# PhatStats_Slim_Enclosure_QTPY_PCB_v1_00_.net
KiCad netlist of a schematic drawn in EAGLE
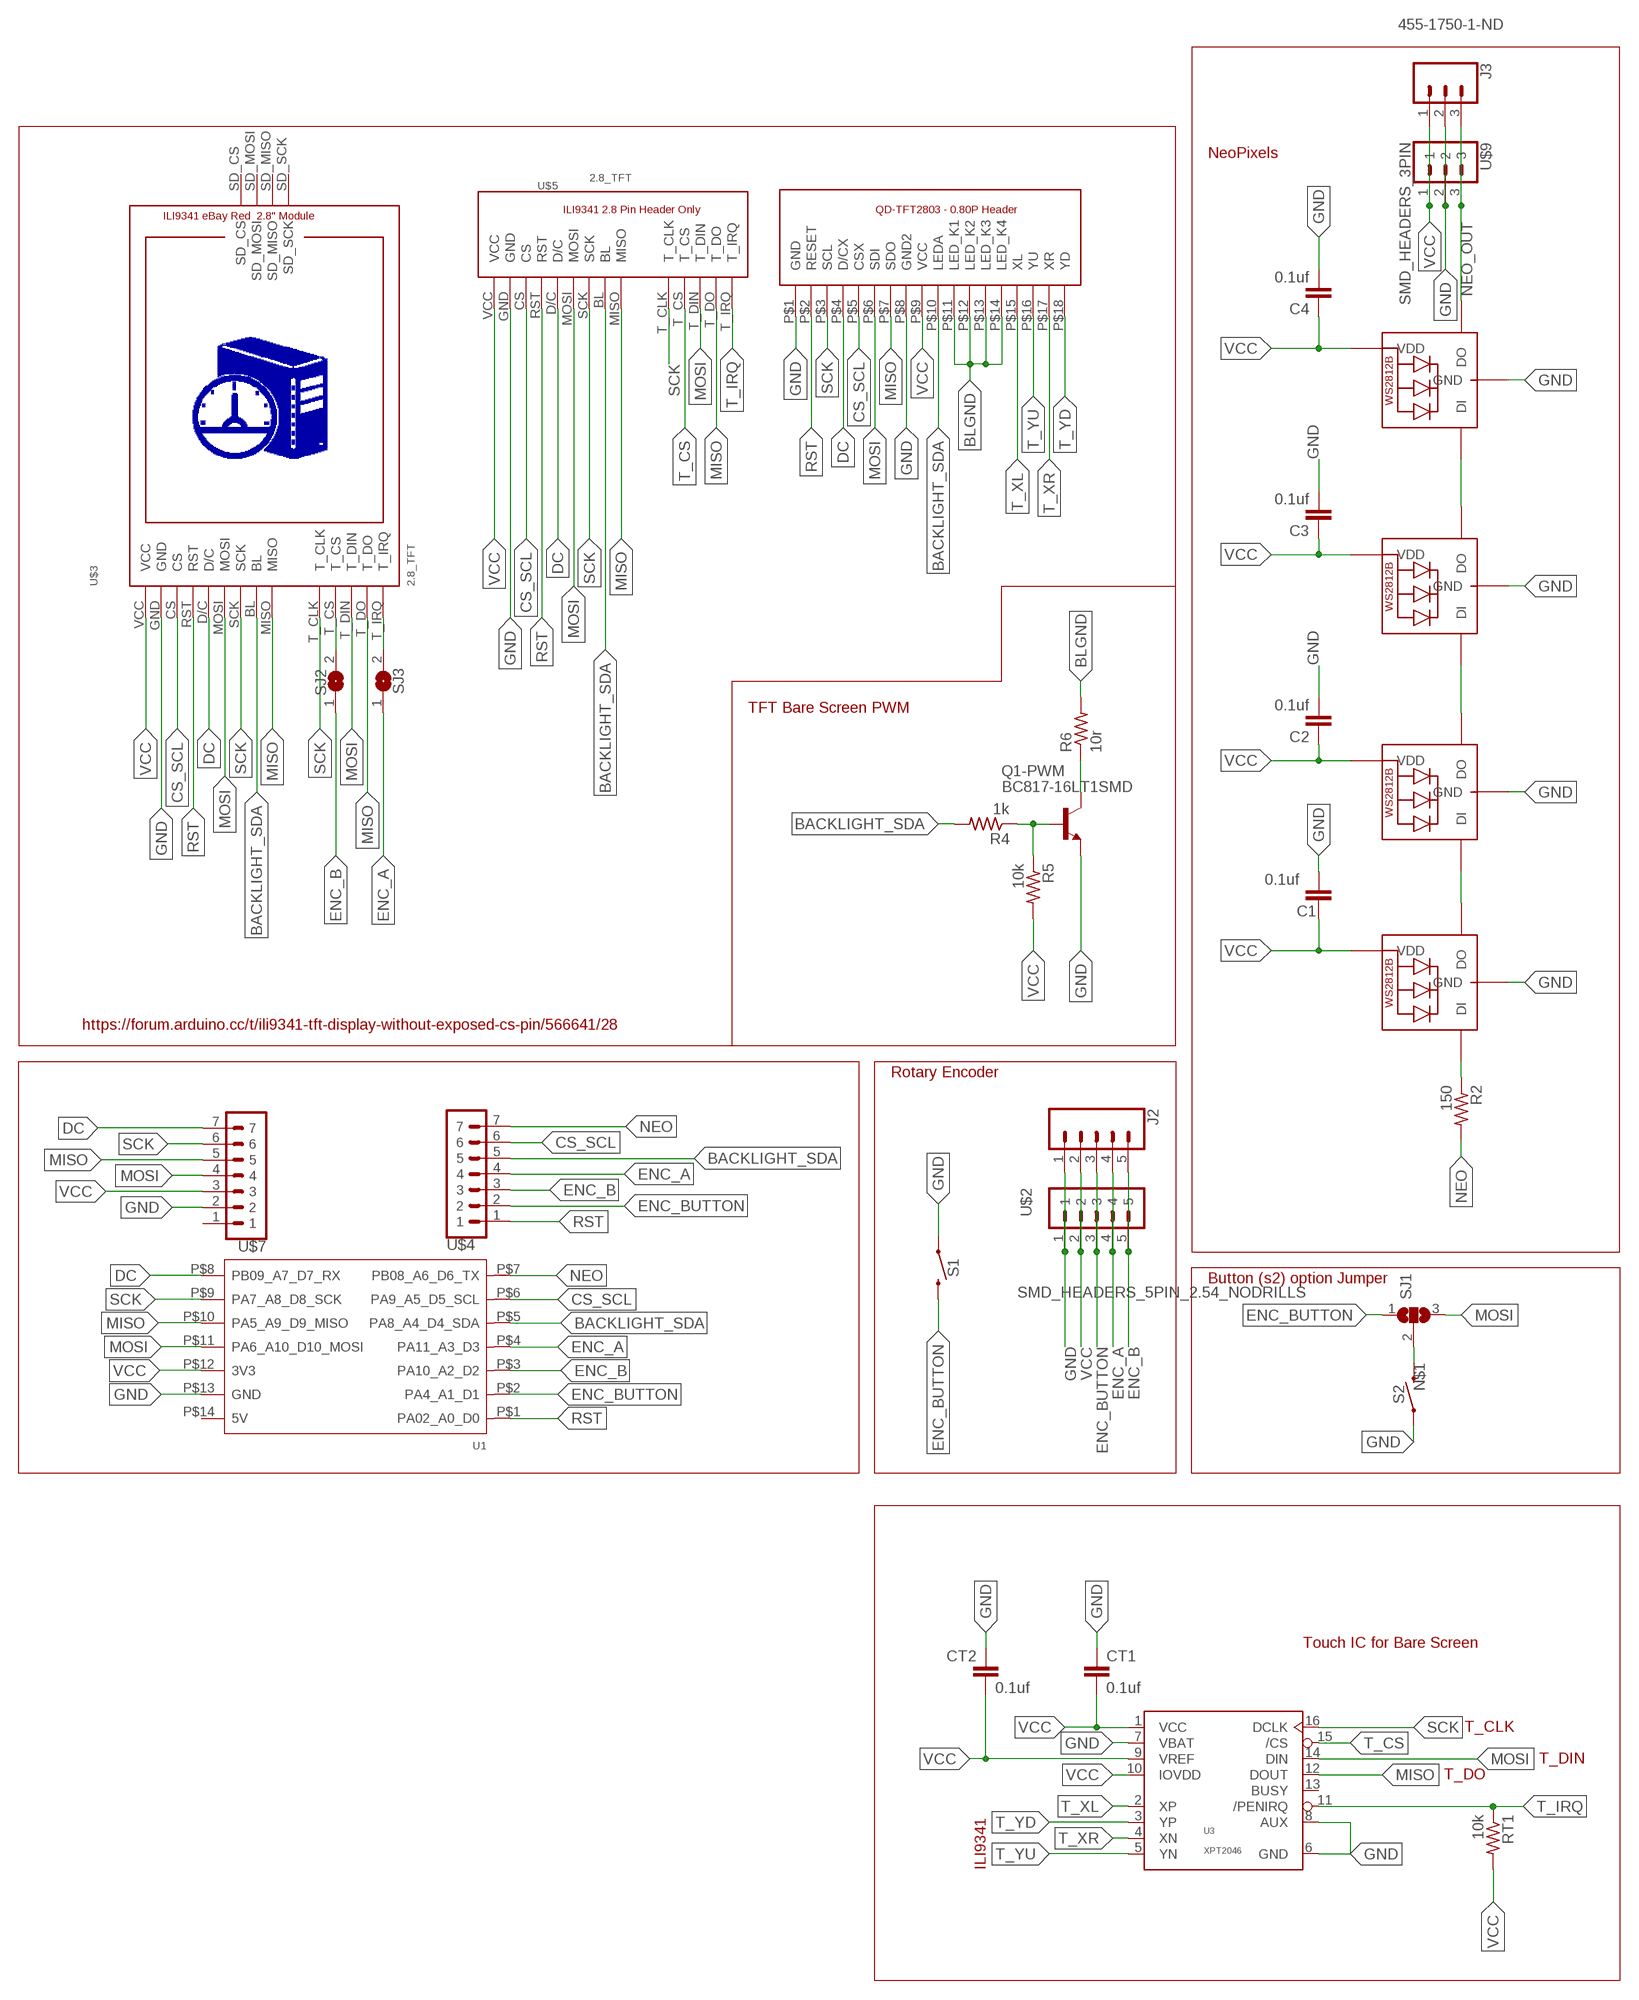
[diagram p0: schematic, sheet 1]

(export (version "E")
  (design (tool "Eeschema 10.0.6"))
  (components
    (comp (ref "0")
      (value "ILI9341-2.8")
      (footprint "eagle-import:ILI9341-2.8")
      (libsource (lib "eagle-import") (part "ILI9341-2.8"))
    )
    (comp (ref "C1")
      (value "0.1uf")
      (footprint "eagle-import:C1206")
      (libsource (lib "eagle-import") (part "C-EUC1206"))
    )
    (comp (ref "C2")
      (value "0.1uf")
      (footprint "eagle-import:C1206")
      (libsource (lib "eagle-import") (part "C-EUC1206"))
    )
    (comp (ref "C3")
      (value "0.1uf")
      (footprint "eagle-import:C1206")
      (libsource (lib "eagle-import") (part "C-EUC1206"))
    )
    (comp (ref "C4")
      (value "0.1uf")
      (footprint "eagle-import:C1206")
      (libsource (lib "eagle-import") (part "C-EUC1206"))
    )
    (comp (ref "CT1")
      (value "0.1uf")
      (footprint "eagle-import:C1206")
      (libsource (lib "eagle-import") (part "C-EUC1206"))
    )
    (comp (ref "CT2")
      (value "0.1uf")
      (footprint "eagle-import:C1206")
      (libsource (lib "eagle-import") (part "C-EUC1206"))
    )
    (comp (ref "J2")
      (value "CONN_05")
      (footprint "eagle-import:1X05")
      (libsource (lib "eagle-import") (part "CONN_05"))
    )
    (comp (ref "J3")
      (value "455-1750-1-ND")
      (footprint "eagle-import:1X03")
      (libsource (lib "eagle-import") (part "CONN_03"))
    )
    (comp (ref "NEO1")
      (value "WS2812B5050")
      (footprint "eagle-import:WS2812B")
      (libsource (lib "eagle-import") (part "WS2812B5050"))
    )
    (comp (ref "NEO2")
      (value "WS2812B5050")
      (footprint "eagle-import:WS2812B")
      (libsource (lib "eagle-import") (part "WS2812B5050"))
    )
    (comp (ref "NEO3")
      (value "WS2812B5050")
      (footprint "eagle-import:WS2812B")
      (libsource (lib "eagle-import") (part "WS2812B5050"))
    )
    (comp (ref "NEO4")
      (value "WS2812B5050")
      (footprint "eagle-import:WS2812B")
      (libsource (lib "eagle-import") (part "WS2812B5050"))
    )
    (comp (ref "Q1-PWM")
      (value "BC817-16LT1SMD")
      (footprint "eagle-import:SOT23-BEC")
      (libsource (lib "eagle-import") (part "BC817SMD-16LT1"))
    )
    (comp (ref "R2")
      (value "150")
      (footprint "eagle-import:M1206")
      (libsource (lib "eagle-import") (part "R-US_M1206"))
    )
    (comp (ref "R4")
      (value "1k")
      (footprint "eagle-import:M1206")
      (libsource (lib "eagle-import") (part "R-US_M1206"))
    )
    (comp (ref "R5")
      (value "10k")
      (footprint "eagle-import:M1206")
      (libsource (lib "eagle-import") (part "R-US_M1206"))
    )
    (comp (ref "R6")
      (value "10r")
      (footprint "eagle-import:M1206")
      (libsource (lib "eagle-import") (part "R-US_M1206"))
    )
    (comp (ref "RT1")
      (value "10k")
      (footprint "eagle-import:M1206")
      (libsource (lib "eagle-import") (part "R-US_M1206"))
    )
    (comp (ref "S1")
      (value "MOMENTARY-SWITCH-SPST-SMD-6.2MM-TALL")
      (footprint "eagle-import:TACTILE_SWITCH_SMD_6.2MM_TALL")
      (libsource (lib "eagle-import") (part "MOMENTARY-SWITCH-SPST-SMD-6.2MM-TALL"))
    )
    (comp (ref "S2")
      (value "MOMENTARY-SWITCH-SPST-SMD-6.2MM-TALL")
      (footprint "eagle-import:TACTILE_SWITCH_SMD_6.2MM_TALL")
      (libsource (lib "eagle-import") (part "MOMENTARY-SWITCH-SPST-SMD-6.2MM-TALL"))
    )
    (comp (ref "SJ1")
      (value "SJ2W")
      (footprint "eagle-import:SJ_2")
      (libsource (lib "eagle-import") (part "SJ2W"))
    )
    (comp (ref "SJ2") (value "SJ") (footprint "eagle-import:SJ") (libsource (lib "eagle-import") (part "SJ")))
    (comp (ref "SJ3") (value "SJ") (footprint "eagle-import:SJ") (libsource (lib "eagle-import") (part "SJ")))
    (comp (ref "U$2")
      (value "SMD_HEADERS_5PIN_2.54_NODRILLS")
      (footprint "eagle-import:SMD_HEADERS_5PIN")
      (libsource (lib "eagle-import") (part "SMD_HEADERS_5PIN_2.54_NODRILLS"))
    )
    (comp (ref "U$3")
      (value "2.8_TFT")
      (footprint "eagle-import:2.8_TFT")
      (libsource (lib "eagle-import") (part "2.8_TFT"))
    )
    (comp (ref "U$4")
      (value "SMD_HEADERS_7PIN_2.54_NODRILLS")
      (footprint "eagle-import:SMD_HEADERS_7PIN")
      (libsource (lib "eagle-import") (part "SMD_HEADERS_7PIN_2.54_NODRILLS"))
    )
    (comp (ref "U$5")
      (value "2.8_TFT")
      (footprint "eagle-import:2.8_TFT")
      (libsource (lib "eagle-import") (part "TML_ili9341-2.8_tft-display_PinHeader only_2.8_TFT"))
    )
    (comp (ref "U$7")
      (value "SMD_HEADERS_7PIN_2.54_NODRILLS")
      (footprint "eagle-import:SMD_HEADERS_7PIN")
      (libsource (lib "eagle-import") (part "SMD_HEADERS_7PIN_2.54_NODRILLS"))
    )
    (comp (ref "U$9")
      (value "SMD_HEADERS_3PIN")
      (footprint "eagle-import:SMD_HEADERS_3PIN")
      (libsource (lib "eagle-import") (part "SMD_HEADERS_3PIN"))
    )
    (comp (ref "U1")
      (value "MOUDLE-SEEEDUINO-XIAO")
      (footprint "eagle-import:MOUDLE14P-2.54-21X17.8MM")
      (libsource (lib "eagle-import") (part "MOUDLE-SEEEDUINO-XIAO"))
    )
    (comp (ref "U3")
      (value "XPT2046")
      (footprint "eagle-import:TSSOP-16")
      (fields (field (name "MF") "Xptek"))
      (libsource (lib "eagle-import") (part "XPT2046"))
    )
  )
  (nets
    (net (code "1") (name "/N$1") (class "Default")
      (node (ref "S2") (pin "B2") (pinfunction "2_B2") (pintype "passive"))
      (node (ref "SJ1") (pin "2") (pinfunction "2_2") (pintype "passive"))
    )
    (net (code "2") (name "/NEO_OUT") (class "Default")
      (node (ref "J3") (pin "3") (pinfunction "3_3") (pintype "passive"))
      (node (ref "NEO4") (pin "2-DOUT") (pinfunction "DO_2-DOUT") (pintype "output"))
      (node (ref "U$9") (pin "3") (pinfunction "3_3") (pintype "passive"))
    )
    (net (code "3") (name "BACKLIGHT_SDA") (class "Default")
      (node (ref "0") (pin "P$10") (pinfunction "LEDA_P$10") (pintype "bidirectional"))
      (node (ref "R4") (pin "2") (pinfunction "2_2") (pintype "passive"))
      (node (ref "U$3") (pin "BL") (pinfunction "BL_BL") (pintype "bidirectional"))
      (node (ref "U$4") (pin "5") (pinfunction "5_5") (pintype "passive"))
      (node (ref "U$5") (pin "BL") (pinfunction "BL_BL") (pintype "bidirectional"))
      (node (ref "U1") (pin "P$5") (pinfunction "PA8_A4_D4_SDA_P$5") (pintype "bidirectional"))
    )
    (net (code "4") (name "BLGND") (class "Default")
      (node (ref "0") (pin "P$11") (pinfunction "LED_K1_P$11") (pintype "bidirectional"))
      (node (ref "0") (pin "P$12") (pinfunction "LED_K2_P$12") (pintype "bidirectional"))
      (node (ref "0") (pin "P$13") (pinfunction "LED_K3_P$13") (pintype "bidirectional"))
      (node (ref "0") (pin "P$14") (pinfunction "LED_K4_P$14") (pintype "bidirectional"))
      (node (ref "R6") (pin "2") (pinfunction "2_2") (pintype "passive"))
    )
    (net (code "5") (name "CS_SCL") (class "Default")
      (node (ref "0") (pin "P$5") (pinfunction "CSX_P$5") (pintype "bidirectional"))
      (node (ref "U$3") (pin "CS") (pinfunction "CS_CS") (pintype "bidirectional"))
      (node (ref "U$4") (pin "6") (pinfunction "6_6") (pintype "passive"))
      (node (ref "U$5") (pin "CS") (pinfunction "CS_CS") (pintype "bidirectional"))
      (node (ref "U1") (pin "P$6") (pinfunction "PA9_A5_D5_SCL_P$6") (pintype "bidirectional"))
    )
    (net (code "6") (name "DC") (class "Default")
      (node (ref "0") (pin "P$4") (pinfunction "D/CX_P$4") (pintype "bidirectional"))
      (node (ref "U$3") (pin "D/C") (pinfunction "D/C_D/C") (pintype "bidirectional"))
      (node (ref "U$5") (pin "D/C") (pinfunction "D/C_D/C") (pintype "bidirectional"))
      (node (ref "U$7") (pin "7") (pinfunction "7_7") (pintype "passive"))
      (node (ref "U1") (pin "P$8") (pinfunction "PB09_A7_D7_RX_P$8") (pintype "bidirectional"))
    )
    (net (code "7") (name "ENC_A") (class "Default")
      (node (ref "J2") (pin "4") (pinfunction "4_4") (pintype "passive"))
      (node (ref "SJ3") (pin "1") (pinfunction "1_1") (pintype "passive"))
      (node (ref "U$2") (pin "4") (pinfunction "4_4") (pintype "passive"))
      (node (ref "U$4") (pin "4") (pinfunction "4_4") (pintype "passive"))
      (node (ref "U1") (pin "P$4") (pinfunction "PA11_A3_D3_P$4") (pintype "bidirectional"))
    )
    (net (code "8") (name "ENC_B") (class "Default")
      (node (ref "J2") (pin "5") (pinfunction "5_5") (pintype "passive"))
      (node (ref "SJ2") (pin "1") (pinfunction "1_1") (pintype "passive"))
      (node (ref "U$2") (pin "5") (pinfunction "5_5") (pintype "passive"))
      (node (ref "U$4") (pin "3") (pinfunction "3_3") (pintype "passive"))
      (node (ref "U1") (pin "P$3") (pinfunction "PA10_A2_D2_P$3") (pintype "bidirectional"))
    )
    (net (code "9") (name "ENC_BUTTON") (class "Default")
      (node (ref "J2") (pin "3") (pinfunction "3_3") (pintype "passive"))
      (node (ref "S1") (pin "B2") (pinfunction "2_B2") (pintype "passive"))
      (node (ref "SJ1") (pin "1") (pinfunction "1_1") (pintype "passive"))
      (node (ref "U$2") (pin "3") (pinfunction "3_3") (pintype "passive"))
      (node (ref "U$4") (pin "2") (pinfunction "2_2") (pintype "passive"))
      (node (ref "U1") (pin "P$2") (pinfunction "PA4_A1_D1_P$2") (pintype "bidirectional"))
    )
    (net (code "10") (name "GND") (class "Default")
      (node (ref "0") (pin "P$1") (pinfunction "GND_P$1") (pintype "bidirectional"))
      (node (ref "0") (pin "P$8") (pinfunction "GND2_P$8") (pintype "bidirectional"))
      (node (ref "C1") (pin "1") (pinfunction "1_1") (pintype "passive"))
      (node (ref "C2") (pin "2") (pinfunction "2_2") (pintype "passive"))
      (node (ref "C3") (pin "2") (pinfunction "2_2") (pintype "passive"))
      (node (ref "C4") (pin "2") (pinfunction "2_2") (pintype "passive"))
      (node (ref "CT1") (pin "1") (pinfunction "1_1") (pintype "passive"))
      (node (ref "CT2") (pin "1") (pinfunction "1_1") (pintype "passive"))
      (node (ref "J2") (pin "1") (pinfunction "1_1") (pintype "passive"))
      (node (ref "J3") (pin "2") (pinfunction "2_2") (pintype "passive"))
      (node (ref "NEO1") (pin "3-GND") (pinfunction "GND_3-GND") (pintype "power_in"))
      (node (ref "NEO2") (pin "3-GND") (pinfunction "GND_3-GND") (pintype "power_in"))
      (node (ref "NEO3") (pin "3-GND") (pinfunction "GND_3-GND") (pintype "power_in"))
      (node (ref "NEO4") (pin "3-GND") (pinfunction "GND_3-GND") (pintype "power_in"))
      (node (ref "Q1-PWM") (pin "E") (pinfunction "E_E") (pintype "passive"))
      (node (ref "S1") (pin "A2") (pinfunction "1_A2") (pintype "passive"))
      (node (ref "S2") (pin "A2") (pinfunction "1_A2") (pintype "passive"))
      (node (ref "U$2") (pin "1") (pinfunction "1_1") (pintype "passive"))
      (node (ref "U$3") (pin "GND") (pinfunction "GND_GND") (pintype "bidirectional"))
      (node (ref "U$5") (pin "GND") (pinfunction "GND_GND") (pintype "bidirectional"))
      (node (ref "U$7") (pin "2") (pinfunction "2_2") (pintype "passive"))
      (node (ref "U$9") (pin "2") (pinfunction "2_2") (pintype "passive"))
      (node (ref "U1") (pin "P$13") (pinfunction "GND_P$13") (pintype "bidirectional"))
      (node (ref "U3") (pin "6") (pinfunction "GND_6") (pintype "power_in"))
      (node (ref "U3") (pin "7") (pinfunction "VBAT_7") (pintype "input"))
      (node (ref "U3") (pin "8") (pinfunction "AUX_8") (pintype "input"))
    )
    (net (code "11") (name "MISO") (class "Default")
      (node (ref "0") (pin "P$7") (pinfunction "SDO_P$7") (pintype "bidirectional"))
      (node (ref "U$3") (pin "MISO") (pinfunction "MISO_MISO") (pintype "bidirectional"))
      (node (ref "U$3") (pin "T_DO") (pinfunction "T_DO_T_DO") (pintype "bidirectional"))
      (node (ref "U$5") (pin "MISO") (pinfunction "MISO_MISO") (pintype "bidirectional"))
      (node (ref "U$5") (pin "T_DO") (pinfunction "T_DO_T_DO") (pintype "bidirectional"))
      (node (ref "U$7") (pin "5") (pinfunction "5_5") (pintype "passive"))
      (node (ref "U1") (pin "P$10") (pinfunction "PA5_A9_D9_MISO_P$10") (pintype "bidirectional"))
      (node (ref "U3") (pin "12") (pinfunction "DOUT_12") (pintype "output"))
    )
    (net (code "12") (name "MOSI") (class "Default")
      (node (ref "0") (pin "P$6") (pinfunction "SDI_P$6") (pintype "bidirectional"))
      (node (ref "SJ1") (pin "3") (pinfunction "3_3") (pintype "passive"))
      (node (ref "U$3") (pin "MOSI") (pinfunction "MOSI_MOSI") (pintype "bidirectional"))
      (node (ref "U$3") (pin "T_DIN") (pinfunction "T_DIN_T_DIN") (pintype "bidirectional"))
      (node (ref "U$5") (pin "MOSI") (pinfunction "MOSI_MOSI") (pintype "bidirectional"))
      (node (ref "U$5") (pin "T_DIN") (pinfunction "T_DIN_T_DIN") (pintype "bidirectional"))
      (node (ref "U$7") (pin "4") (pinfunction "4_4") (pintype "passive"))
      (node (ref "U1") (pin "P$11") (pinfunction "PA6_A10_D10_MOSI_P$11") (pintype "bidirectional"))
      (node (ref "U3") (pin "14") (pinfunction "DIN_14") (pintype "input"))
    )
    (net (code "13") (name "NEO") (class "Default")
      (node (ref "R2") (pin "2") (pinfunction "2_2") (pintype "passive"))
      (node (ref "U$4") (pin "7") (pinfunction "7_7") (pintype "passive"))
      (node (ref "U1") (pin "P$7") (pinfunction "PB08_A6_D6_TX_P$7") (pintype "bidirectional"))
    )
    (net (code "14") (name "Net-(NEO1-DI)") (class "Default")
      (node (ref "NEO1") (pin "4-DIN") (pinfunction "DI_4-DIN") (pintype "input"))
      (node (ref "R2") (pin "1") (pinfunction "1_1") (pintype "passive"))
    )
    (net (code "15") (name "Net-(NEO1-DO)") (class "Default")
      (node (ref "NEO1") (pin "2-DOUT") (pinfunction "DO_2-DOUT") (pintype "output"))
      (node (ref "NEO2") (pin "4-DIN") (pinfunction "DI_4-DIN") (pintype "input"))
    )
    (net (code "16") (name "Net-(NEO2-DO)") (class "Default")
      (node (ref "NEO2") (pin "2-DOUT") (pinfunction "DO_2-DOUT") (pintype "output"))
      (node (ref "NEO3") (pin "4-DIN") (pinfunction "DI_4-DIN") (pintype "input"))
    )
    (net (code "17") (name "Net-(NEO3-DO)") (class "Default")
      (node (ref "NEO3") (pin "2-DOUT") (pinfunction "DO_2-DOUT") (pintype "output"))
      (node (ref "NEO4") (pin "4-DIN") (pinfunction "DI_4-DIN") (pintype "input"))
    )
    (net (code "18") (name "Net-(Q1-PWM-PadB)") (class "Default")
      (node (ref "Q1-PWM") (pin "B") (pinfunction "B_B") (pintype "passive"))
      (node (ref "R4") (pin "1") (pinfunction "1_1") (pintype "passive"))
      (node (ref "R5") (pin "1") (pinfunction "1_1") (pintype "passive"))
    )
    (net (code "19") (name "Net-(Q1-PWM-PadC)") (class "Default")
      (node (ref "Q1-PWM") (pin "C") (pinfunction "C_C") (pintype "passive"))
      (node (ref "R6") (pin "1") (pinfunction "1_1") (pintype "passive"))
    )
    (net (code "20") (name "RST") (class "Default")
      (node (ref "0") (pin "P$2") (pinfunction "RESET_P$2") (pintype "bidirectional"))
      (node (ref "U$3") (pin "RST") (pinfunction "RST_RST") (pintype "bidirectional"))
      (node (ref "U$4") (pin "1") (pinfunction "1_1") (pintype "passive"))
      (node (ref "U$5") (pin "RST") (pinfunction "RST_RST") (pintype "bidirectional"))
      (node (ref "U1") (pin "P$1") (pinfunction "PA02_A0_D0_P$1") (pintype "bidirectional"))
    )
    (net (code "21") (name "SCK") (class "Default")
      (node (ref "0") (pin "P$3") (pinfunction "SCL_P$3") (pintype "bidirectional"))
      (node (ref "U$3") (pin "SCK") (pinfunction "SCK_SCK") (pintype "bidirectional"))
      (node (ref "U$3") (pin "T_CLK") (pinfunction "T_CLK_T_CLK") (pintype "bidirectional"))
      (node (ref "U$5") (pin "SCK") (pinfunction "SCK_SCK") (pintype "bidirectional"))
      (node (ref "U$5") (pin "T_CLK") (pinfunction "T_CLK_T_CLK") (pintype "bidirectional"))
      (node (ref "U$7") (pin "6") (pinfunction "6_6") (pintype "passive"))
      (node (ref "U1") (pin "P$9") (pinfunction "PA7_A8_D8_SCK_P$9") (pintype "bidirectional"))
      (node (ref "U3") (pin "16") (pinfunction "DCLK_16") (pintype "input"))
    )
    (net (code "22") (name "T_CS") (class "Default")
      (node (ref "SJ2") (pin "2") (pinfunction "2_2") (pintype "passive"))
      (node (ref "U$3") (pin "T_CS") (pinfunction "T_CS_T_CS") (pintype "bidirectional"))
      (node (ref "U$5") (pin "T_CS") (pinfunction "T_CS_T_CS") (pintype "bidirectional"))
      (node (ref "U3") (pin "15") (pinfunction "/CS_15") (pintype "input"))
    )
    (net (code "23") (name "T_IRQ") (class "Default")
      (node (ref "RT1") (pin "1") (pinfunction "1_1") (pintype "passive"))
      (node (ref "SJ3") (pin "2") (pinfunction "2_2") (pintype "passive"))
      (node (ref "U$3") (pin "T_IRQ") (pinfunction "T_IRQ_T_IRQ") (pintype "bidirectional"))
      (node (ref "U$5") (pin "T_IRQ") (pinfunction "T_IRQ_T_IRQ") (pintype "bidirectional"))
      (node (ref "U3") (pin "11") (pinfunction "/PENIRQ_11") (pintype "output"))
    )
    (net (code "24") (name "T_XL") (class "Default")
      (node (ref "0") (pin "P$15") (pinfunction "XL_P$15") (pintype "bidirectional"))
      (node (ref "U3") (pin "2") (pinfunction "XP_2") (pintype "input"))
    )
    (net (code "25") (name "T_XR") (class "Default")
      (node (ref "0") (pin "P$17") (pinfunction "XR_P$17") (pintype "bidirectional"))
      (node (ref "U3") (pin "4") (pinfunction "XN_4") (pintype "input"))
    )
    (net (code "26") (name "T_YD") (class "Default")
      (node (ref "0") (pin "P$18") (pinfunction "YD_P$18") (pintype "bidirectional"))
      (node (ref "U3") (pin "3") (pinfunction "YP_3") (pintype "input"))
    )
    (net (code "27") (name "T_YU") (class "Default")
      (node (ref "0") (pin "P$16") (pinfunction "YU_P$16") (pintype "bidirectional"))
      (node (ref "U3") (pin "5") (pinfunction "YN_5") (pintype "input"))
    )
    (net (code "28") (name "VCC") (class "Default")
      (node (ref "0") (pin "P$9") (pinfunction "VCC_P$9") (pintype "bidirectional"))
      (node (ref "C1") (pin "2") (pinfunction "2_2") (pintype "passive"))
      (node (ref "C2") (pin "1") (pinfunction "1_1") (pintype "passive"))
      (node (ref "C3") (pin "1") (pinfunction "1_1") (pintype "passive"))
      (node (ref "C4") (pin "1") (pinfunction "1_1") (pintype "passive"))
      (node (ref "CT1") (pin "2") (pinfunction "2_2") (pintype "passive"))
      (node (ref "CT2") (pin "2") (pinfunction "2_2") (pintype "passive"))
      (node (ref "J2") (pin "2") (pinfunction "2_2") (pintype "passive"))
      (node (ref "J3") (pin "1") (pinfunction "1_1") (pintype "passive"))
      (node (ref "NEO1") (pin "1-VDD") (pinfunction "VDD_1-VDD") (pintype "power_in"))
      (node (ref "NEO2") (pin "1-VDD") (pinfunction "VDD_1-VDD") (pintype "power_in"))
      (node (ref "NEO3") (pin "1-VDD") (pinfunction "VDD_1-VDD") (pintype "power_in"))
      (node (ref "NEO4") (pin "1-VDD") (pinfunction "VDD_1-VDD") (pintype "power_in"))
      (node (ref "R5") (pin "2") (pinfunction "2_2") (pintype "passive"))
      (node (ref "RT1") (pin "2") (pinfunction "2_2") (pintype "passive"))
      (node (ref "U$2") (pin "2") (pinfunction "2_2") (pintype "passive"))
      (node (ref "U$3") (pin "VCC") (pinfunction "VCC_VCC") (pintype "bidirectional"))
      (node (ref "U$5") (pin "VCC") (pinfunction "VCC_VCC") (pintype "bidirectional"))
      (node (ref "U$7") (pin "3") (pinfunction "3_3") (pintype "passive"))
      (node (ref "U$9") (pin "1") (pinfunction "1_1") (pintype "passive"))
      (node (ref "U1") (pin "P$12") (pinfunction "3V3_P$12") (pintype "bidirectional"))
      (node (ref "U3") (pin "1") (pinfunction "VCC_1") (pintype "power_in"))
      (node (ref "U3") (pin "10") (pinfunction "IOVDD_10") (pintype "power_in"))
      (node (ref "U3") (pin "9") (pinfunction "VREF_9") (pintype "input"))
    )
    (net (code "29") (name "unconnected-(U$3-PadSD_CS)") (class "Default")
      (node (ref "U$3") (pin "SD_CS") (pinfunction "SD_CS_SD_CS") (pintype "bidirectional"))
    )
    (net (code "30") (name "unconnected-(U$3-PadSD_MISO)") (class "Default")
      (node (ref "U$3") (pin "SD_MISO") (pinfunction "SD_MISO_SD_MISO") (pintype "bidirectional"))
    )
    (net (code "31") (name "unconnected-(U$3-PadSD_MOSI)") (class "Default")
      (node (ref "U$3") (pin "SD_MOSI") (pinfunction "SD_MOSI_SD_MOSI") (pintype "bidirectional"))
    )
    (net (code "32") (name "unconnected-(U$3-PadSD_SCK)") (class "Default")
      (node (ref "U$3") (pin "SD_SCK") (pinfunction "SD_SCK_SD_SCK") (pintype "bidirectional"))
    )
    (net (code "33") (name "unconnected-(U$7-Pad1)") (class "Default")
      (node (ref "U$7") (pin "1") (pinfunction "1_1") (pintype "passive"))
    )
    (net (code "34") (name "unconnected-(U1-5V-PadP$14)") (class "Default")
      (node (ref "U1") (pin "P$14") (pinfunction "5V_P$14") (pintype "bidirectional"))
    )
    (net (code "35") (name "unconnected-(U3-BUSY-Pad13)") (class "Default")
      (node (ref "U3") (pin "13") (pinfunction "BUSY_13") (pintype "output"))
    )
  )
)
